# CANSAT_Telemetry_schematic.net
KiCad netlist of a schematic drawn in Altium Designer
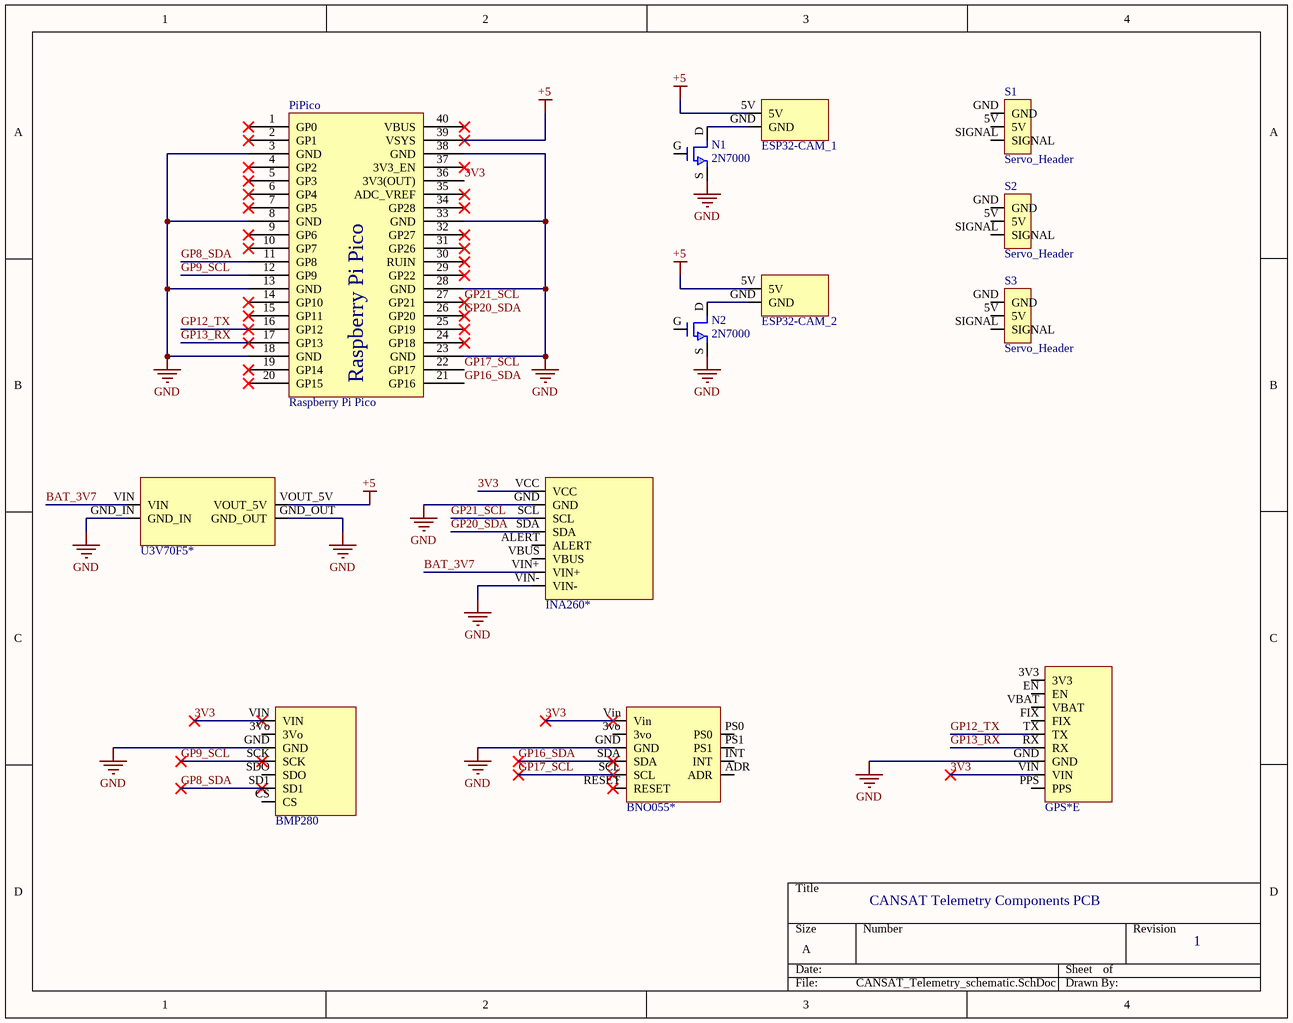
[diagram p0: CANSAT_Telemetry_schematic.SchDoc]

(export (version "E")
  (design (tool "Eeschema 10.0.6"))
  (components
    (comp (ref "BMP280")
      (value "BMP280")
      (footprint "BMP280_BreakoutBoard")
      (libsource (lib "CANSAT_ExtraLib") (part "BMP280_BreakoutBoard"))
    )
    (comp (ref "BNO055*")
      (value "BNO055*")
      (footprint "BNO055_BreakoutBoard")
      (libsource (lib "CANSAT_ExtraLib") (part "BNO055"))
    )
    (comp (ref "ESP32-CAM_1")
      (value "ESP32-CAM_1")
      (footprint "ESP32-CAM")
      (libsource (lib "CANSAT_ExtraLib") (part "ESP32-CAM"))
    )
    (comp (ref "ESP32-CAM_2")
      (value "ESP32-CAM_2")
      (footprint "ESP32-CAM")
      (libsource (lib "CANSAT_ExtraLib") (part "ESP32-CAM"))
    )
    (comp (ref "GPS*")
      (value "GPS*")
      (footprint "AdafruitUltimateGPS")
      (libsource (lib "CANSAT_ExtraLib") (part "AdafruitUltimateGPS"))
    )
    (comp (ref "INA260*")
      (value "INA260*")
      (footprint "INA260_Breakout")
      (libsource (lib "CANSAT_ExtraLib") (part "INA260_Breakout"))
    )
    (comp (ref "N1")
      (value "2N7000")
      (footprint "2N7000")
      (libsource (lib "CANSAT_ExtraLib") (part "2N7000"))
    )
    (comp (ref "N2")
      (value "2N7000")
      (footprint "2N7000")
      (libsource (lib "CANSAT_ExtraLib") (part "2N7000"))
    )
    (comp (ref "PiPico")
      (value "Raspberry Pi Pico")
      (footprint "Raspberry Pi Pico")
      (libsource (lib "ECE Lib 22") (part "Raspberry Pi Pico"))
    )
    (comp (ref "S1") (value "Servo_Header") (libsource (lib "CANSAT_ExtraLib") (part "Servo_Header")))
    (comp (ref "S2") (value "Servo_Header") (libsource (lib "CANSAT_ExtraLib") (part "Servo_Header")))
    (comp (ref "S3") (value "Servo_Header") (libsource (lib "CANSAT_ExtraLib") (part "Servo_Header")))
    (comp (ref "U3V70F5*")
      (value "U3V70F5*")
      (footprint "U3V70F5")
      (description "Boost Regulator: 5V")
      (libsource (lib "CANSAT_ExtraLib") (part "U3V70F5"))
    )
  )
  (nets
    (net (code "1") (name "+5") (class "Default")
      (node (ref "ESP32-CAM_1") (pin "5V") (pinfunction "5V_5V") (pintype "passive"))
      (node (ref "ESP32-CAM_2") (pin "5V") (pinfunction "5V_5V") (pintype "passive"))
      (node (ref "PiPico") (pin "39") (pinfunction "VSYS_39") (pintype "passive"))
      (node (ref "U3V70F5*") (pin "VOUT_5V") (pinfunction "VOUT_5V_VOUT_5V") (pintype "passive"))
    )
    (net (code "2") (name "/3V3") (class "Default")
      (node (ref "BMP280") (pin "VIN") (pinfunction "VIN_VIN") (pintype "passive"))
      (node (ref "BNO055*") (pin "Vin") (pinfunction "Vin_Vin") (pintype "passive"))
      (node (ref "GPS*") (pin "VIN") (pinfunction "VIN_VIN") (pintype "passive"))
      (node (ref "INA260*") (pin "VCC") (pinfunction "VCC_VCC") (pintype "passive"))
      (node (ref "PiPico") (pin "36") (pinfunction "3V3(OUT)_36") (pintype "passive"))
    )
    (net (code "3") (name "/BAT_3V7") (class "Default")
      (node (ref "INA260*") (pin "VIN+") (pinfunction "VIN+_VIN+") (pintype "passive"))
      (node (ref "U3V70F5*") (pin "VIN") (pinfunction "VIN_VIN") (pintype "passive"))
    )
    (net (code "4") (name "/GP8_SDA") (class "Default")
      (node (ref "BMP280") (pin "SD1") (pinfunction "SD1_SD1") (pintype "passive"))
      (node (ref "PiPico") (pin "11") (pinfunction "GP8_11") (pintype "passive"))
    )
    (net (code "5") (name "/GP9_SCL") (class "Default")
      (node (ref "BMP280") (pin "SCK") (pinfunction "SCK_SCK") (pintype "passive"))
      (node (ref "PiPico") (pin "12") (pinfunction "GP9_12") (pintype "passive"))
    )
    (net (code "6") (name "/GP12_TX") (class "Default")
      (node (ref "GPS*") (pin "TX") (pinfunction "TX_TX") (pintype "passive"))
      (node (ref "PiPico") (pin "16") (pinfunction "GP12_16") (pintype "passive"))
    )
    (net (code "7") (name "/GP13_RX") (class "Default")
      (node (ref "GPS*") (pin "RX") (pinfunction "RX_RX") (pintype "passive"))
      (node (ref "PiPico") (pin "17") (pinfunction "GP13_17") (pintype "passive"))
    )
    (net (code "8") (name "/GP16_SDA") (class "Default")
      (node (ref "BNO055*") (pin "SDA") (pinfunction "SDA_SDA") (pintype "passive"))
      (node (ref "PiPico") (pin "21") (pinfunction "GP16_21") (pintype "passive"))
    )
    (net (code "9") (name "/GP17_SCL") (class "Default")
      (node (ref "BNO055*") (pin "SCL") (pinfunction "SCL_SCL") (pintype "passive"))
      (node (ref "PiPico") (pin "22") (pinfunction "GP17_22") (pintype "passive"))
    )
    (net (code "10") (name "/GP20_SDA") (class "Default")
      (node (ref "INA260*") (pin "SDA") (pinfunction "SDA_SDA") (pintype "passive"))
      (node (ref "PiPico") (pin "26") (pinfunction "GP20_26") (pintype "passive"))
    )
    (net (code "11") (name "/GP21_SCL") (class "Default")
      (node (ref "INA260*") (pin "SCL") (pinfunction "SCL_SCL") (pintype "passive"))
      (node (ref "PiPico") (pin "27") (pinfunction "GP21_27") (pintype "passive"))
    )
    (net (code "12") (name "GND") (class "Default")
      (node (ref "BMP280") (pin "GND") (pinfunction "GND_GND") (pintype "passive"))
      (node (ref "BNO055*") (pin "GND") (pinfunction "GND_GND") (pintype "passive"))
      (node (ref "GPS*") (pin "GND") (pinfunction "GND_GND") (pintype "passive"))
      (node (ref "INA260*") (pin "GND") (pinfunction "GND_GND") (pintype "passive"))
      (node (ref "INA260*") (pin "VIN-") (pinfunction "VIN-_VIN-") (pintype "passive"))
      (node (ref "N1") (pin "S") (pinfunction "S_S") (pintype "passive"))
      (node (ref "N2") (pin "S") (pinfunction "S_S") (pintype "passive"))
      (node (ref "PiPico") (pin "13") (pinfunction "GND_13") (pintype "passive"))
      (node (ref "PiPico") (pin "18") (pinfunction "GND_18") (pintype "passive"))
      (node (ref "PiPico") (pin "23") (pinfunction "GND_23") (pintype "passive"))
      (node (ref "PiPico") (pin "28") (pinfunction "GND_28") (pintype "passive"))
      (node (ref "PiPico") (pin "3") (pinfunction "GND_3") (pintype "passive"))
      (node (ref "PiPico") (pin "33") (pinfunction "GND_33") (pintype "passive"))
      (node (ref "PiPico") (pin "38") (pinfunction "GND_38") (pintype "passive"))
      (node (ref "PiPico") (pin "8") (pinfunction "GND_8") (pintype "passive"))
      (node (ref "U3V70F5*") (pin "GND_IN") (pinfunction "GND_IN_GND_IN") (pintype "passive"))
      (node (ref "U3V70F5*") (pin "GND_OUT") (pinfunction "GND_OUT_GND_OUT") (pintype "passive"))
    )
    (net (code "13") (name "Net-(ESP32-CAM_1-PadGND)") (class "Default")
      (node (ref "ESP32-CAM_1") (pin "GND") (pinfunction "GND_GND") (pintype "passive"))
      (node (ref "N1") (pin "D") (pinfunction "D_D") (pintype "passive"))
    )
    (net (code "14") (name "Net-(ESP32-CAM_2-PadGND)") (class "Default")
      (node (ref "ESP32-CAM_2") (pin "GND") (pinfunction "GND_GND") (pintype "passive"))
      (node (ref "N2") (pin "D") (pinfunction "D_D") (pintype "passive"))
    )
    (net (code "15") (name "unconnected-(BMP280-Pad3Vo)") (class "Default")
      (node (ref "BMP280") (pin "3Vo") (pinfunction "3Vo_3Vo") (pintype "passive"))
    )
    (net (code "16") (name "unconnected-(BMP280-PadCS)") (class "Default")
      (node (ref "BMP280") (pin "CS") (pinfunction "CS_CS") (pintype "passive"))
    )
    (net (code "17") (name "unconnected-(BMP280-PadSDO)") (class "Default")
      (node (ref "BMP280") (pin "SDO") (pinfunction "SDO_SDO") (pintype "passive"))
    )
    (net (code "18") (name "unconnected-(BNO055*-Pad3vo)") (class "Default")
      (node (ref "BNO055*") (pin "3vo") (pinfunction "3vo_3vo") (pintype "passive"))
    )
    (net (code "19") (name "unconnected-(BNO055*-PadADR)") (class "Default")
      (node (ref "BNO055*") (pin "ADR") (pinfunction "ADR_ADR") (pintype "passive"))
    )
    (net (code "20") (name "unconnected-(BNO055*-PadINT)") (class "Default")
      (node (ref "BNO055*") (pin "INT") (pinfunction "INT_INT") (pintype "passive"))
    )
    (net (code "21") (name "unconnected-(BNO055*-PadPS0)") (class "Default")
      (node (ref "BNO055*") (pin "PS0") (pinfunction "PS0_PS0") (pintype "passive"))
    )
    (net (code "22") (name "unconnected-(BNO055*-PadPS1)") (class "Default")
      (node (ref "BNO055*") (pin "PS1") (pinfunction "PS1_PS1") (pintype "passive"))
    )
    (net (code "23") (name "unconnected-(BNO055*-PadRESET)") (class "Default")
      (node (ref "BNO055*") (pin "RESET") (pinfunction "RESET_RESET") (pintype "passive+no_connect"))
    )
    (net (code "24") (name "unconnected-(GPS*-Pad3V3)") (class "Default")
      (node (ref "GPS*") (pin "3V3") (pinfunction "3V3_3V3") (pintype "passive"))
    )
    (net (code "25") (name "unconnected-(GPS*-PadEN)") (class "Default")
      (node (ref "GPS*") (pin "EN") (pinfunction "EN_EN") (pintype "passive"))
    )
    (net (code "26") (name "unconnected-(GPS*-PadFIX)") (class "Default")
      (node (ref "GPS*") (pin "FIX") (pinfunction "FIX_FIX") (pintype "passive"))
    )
    (net (code "27") (name "unconnected-(GPS*-PadPPS)") (class "Default")
      (node (ref "GPS*") (pin "PPS") (pinfunction "PPS_PPS") (pintype "passive"))
    )
    (net (code "28") (name "unconnected-(GPS*-PadVBAT)") (class "Default")
      (node (ref "GPS*") (pin "VBAT") (pinfunction "VBAT_VBAT") (pintype "passive"))
    )
    (net (code "29") (name "unconnected-(INA260*-PadALERT)") (class "Default")
      (node (ref "INA260*") (pin "ALERT") (pinfunction "ALERT_ALERT") (pintype "passive"))
    )
    (net (code "30") (name "unconnected-(INA260*-PadVBUS)") (class "Default")
      (node (ref "INA260*") (pin "VBUS") (pinfunction "VBUS_VBUS") (pintype "passive"))
    )
    (net (code "31") (name "unconnected-(N1-PadG)") (class "Default")
      (node (ref "N1") (pin "G") (pinfunction "G_G") (pintype "passive"))
    )
    (net (code "32") (name "unconnected-(N2-PadG)") (class "Default")
      (node (ref "N2") (pin "G") (pinfunction "G_G") (pintype "passive"))
    )
    (net (code "33") (name "unconnected-(PiPico-3V3_EN-Pad37)") (class "Default")
      (node (ref "PiPico") (pin "37") (pinfunction "3V3_EN_37") (pintype "passive+no_connect"))
    )
    (net (code "34") (name "unconnected-(PiPico-ADC_VREF-Pad35)") (class "Default")
      (node (ref "PiPico") (pin "35") (pinfunction "ADC_VREF_35") (pintype "passive+no_connect"))
    )
    (net (code "35") (name "unconnected-(PiPico-GP0-Pad1)") (class "Default")
      (node (ref "PiPico") (pin "1") (pinfunction "GP0_1") (pintype "passive+no_connect"))
    )
    (net (code "36") (name "unconnected-(PiPico-GP1-Pad2)") (class "Default")
      (node (ref "PiPico") (pin "2") (pinfunction "GP1_2") (pintype "passive+no_connect"))
    )
    (net (code "37") (name "unconnected-(PiPico-GP2-Pad4)") (class "Default")
      (node (ref "PiPico") (pin "4") (pinfunction "GP2_4") (pintype "passive+no_connect"))
    )
    (net (code "38") (name "unconnected-(PiPico-GP3-Pad5)") (class "Default")
      (node (ref "PiPico") (pin "5") (pinfunction "GP3_5") (pintype "passive+no_connect"))
    )
    (net (code "39") (name "unconnected-(PiPico-GP4-Pad6)") (class "Default")
      (node (ref "PiPico") (pin "6") (pinfunction "GP4_6") (pintype "passive+no_connect"))
    )
    (net (code "40") (name "unconnected-(PiPico-GP5-Pad7)") (class "Default")
      (node (ref "PiPico") (pin "7") (pinfunction "GP5_7") (pintype "passive+no_connect"))
    )
    (net (code "41") (name "unconnected-(PiPico-GP6-Pad9)") (class "Default")
      (node (ref "PiPico") (pin "9") (pinfunction "GP6_9") (pintype "passive+no_connect"))
    )
    (net (code "42") (name "unconnected-(PiPico-GP7-Pad10)") (class "Default")
      (node (ref "PiPico") (pin "10") (pinfunction "GP7_10") (pintype "passive+no_connect"))
    )
    (net (code "43") (name "unconnected-(PiPico-GP10-Pad14)") (class "Default")
      (node (ref "PiPico") (pin "14") (pinfunction "GP10_14") (pintype "passive+no_connect"))
    )
    (net (code "44") (name "unconnected-(PiPico-GP11-Pad15)") (class "Default")
      (node (ref "PiPico") (pin "15") (pinfunction "GP11_15") (pintype "passive+no_connect"))
    )
    (net (code "45") (name "unconnected-(PiPico-GP14-Pad19)") (class "Default")
      (node (ref "PiPico") (pin "19") (pinfunction "GP14_19") (pintype "passive+no_connect"))
    )
    (net (code "46") (name "unconnected-(PiPico-GP15-Pad20)") (class "Default")
      (node (ref "PiPico") (pin "20") (pinfunction "GP15_20") (pintype "passive+no_connect"))
    )
    (net (code "47") (name "unconnected-(PiPico-GP18-Pad24)") (class "Default")
      (node (ref "PiPico") (pin "24") (pinfunction "GP18_24") (pintype "passive+no_connect"))
    )
    (net (code "48") (name "unconnected-(PiPico-GP19-Pad25)") (class "Default")
      (node (ref "PiPico") (pin "25") (pinfunction "GP19_25") (pintype "passive+no_connect"))
    )
    (net (code "49") (name "unconnected-(PiPico-GP22-Pad29)") (class "Default")
      (node (ref "PiPico") (pin "29") (pinfunction "GP22_29") (pintype "passive+no_connect"))
    )
    (net (code "50") (name "unconnected-(PiPico-GP26-Pad31)") (class "Default")
      (node (ref "PiPico") (pin "31") (pinfunction "GP26_31") (pintype "passive+no_connect"))
    )
    (net (code "51") (name "unconnected-(PiPico-GP27-Pad32)") (class "Default")
      (node (ref "PiPico") (pin "32") (pinfunction "GP27_32") (pintype "passive+no_connect"))
    )
    (net (code "52") (name "unconnected-(PiPico-GP28-Pad34)") (class "Default")
      (node (ref "PiPico") (pin "34") (pinfunction "GP28_34") (pintype "passive+no_connect"))
    )
    (net (code "53") (name "unconnected-(PiPico-RUIN-Pad30)") (class "Default")
      (node (ref "PiPico") (pin "30") (pinfunction "RUIN_30") (pintype "passive+no_connect"))
    )
    (net (code "54") (name "unconnected-(PiPico-VBUS-Pad40)") (class "Default")
      (node (ref "PiPico") (pin "40") (pinfunction "VBUS_40") (pintype "passive+no_connect"))
    )
    (net (code "55") (name "unconnected-(S1-Pad5V)") (class "Default")
      (node (ref "S1") (pin "5V") (pinfunction "5V_5V") (pintype "passive"))
    )
    (net (code "56") (name "unconnected-(S1-PadGND)") (class "Default")
      (node (ref "S1") (pin "GND") (pinfunction "GND_GND") (pintype "passive"))
    )
    (net (code "57") (name "unconnected-(S1-PadSIGNAL)") (class "Default")
      (node (ref "S1") (pin "SIGNAL") (pinfunction "SIGNAL_SIGNAL") (pintype "passive"))
    )
    (net (code "58") (name "unconnected-(S2-Pad5V)") (class "Default")
      (node (ref "S2") (pin "5V") (pinfunction "5V_5V") (pintype "passive"))
    )
    (net (code "59") (name "unconnected-(S2-PadGND)") (class "Default")
      (node (ref "S2") (pin "GND") (pinfunction "GND_GND") (pintype "passive"))
    )
    (net (code "60") (name "unconnected-(S2-PadSIGNAL)") (class "Default")
      (node (ref "S2") (pin "SIGNAL") (pinfunction "SIGNAL_SIGNAL") (pintype "passive"))
    )
    (net (code "61") (name "unconnected-(S3-Pad5V)") (class "Default")
      (node (ref "S3") (pin "5V") (pinfunction "5V_5V") (pintype "passive"))
    )
    (net (code "62") (name "unconnected-(S3-PadGND)") (class "Default")
      (node (ref "S3") (pin "GND") (pinfunction "GND_GND") (pintype "passive"))
    )
    (net (code "63") (name "unconnected-(S3-PadSIGNAL)") (class "Default")
      (node (ref "S3") (pin "SIGNAL") (pinfunction "SIGNAL_SIGNAL") (pintype "passive"))
    )
  )
)
